# servos.net
KiCad netlist of a schematic drawn in Altium Designer
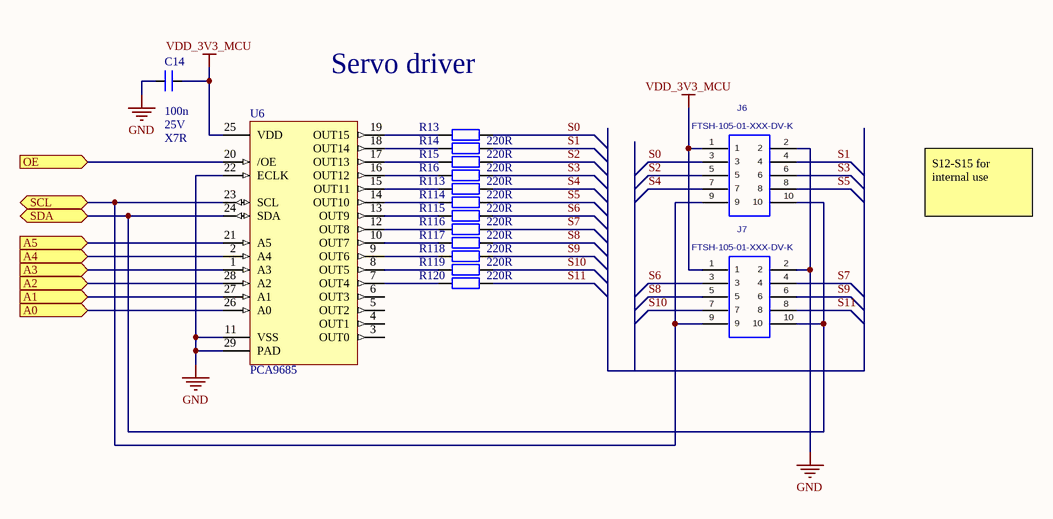
[diagram p0: servos.SchDoc]

(export (version "E")
  (design (tool "Eeschema 10.0.6"))
  (components
    (comp (ref "C14")
      (value "100n")
      (footprint "C1005[0402]")
      (description "Capacitor")
      (fields (field (name "VOLTAGE") "25V") (field (name "TYPE") "X7R") (field (name "Comment") "cap"))
      (libsource (lib "gpa_passives") (part "cap"))
    )
    (comp (ref "J6")
      (value "FTSH-105-01-XXX-DV-K")
      (footprint "FTSH-105-01-XXX-DV-K")
      (description "TERMINAL STRIP, .050\"(1.27mm) PITCH, 10 PINS, KEYED")
      (fields (field (name "MANUFACTURER") "SAMTEC") (field (name "CREATED") "November 30, 2016 - Wendy Xin"))
      (libsource (lib "FTSH-105-01-XXX-DV-K") (part "FTSH-105-01-XXX-DV-K"))
    )
    (comp (ref "J7")
      (value "FTSH-105-01-XXX-DV-K")
      (footprint "FTSH-105-01-XXX-DV-K")
      (description "TERMINAL STRIP, .050\"(1.27mm) PITCH, 10 PINS, KEYED")
      (fields (field (name "MANUFACTURER") "SAMTEC") (field (name "CREATED") "November 30, 2016 - Wendy Xin"))
      (libsource (lib "FTSH-105-01-XXX-DV-K") (part "FTSH-105-01-XXX-DV-K"))
    )
    (comp (ref "R13")
      (value "220R")
      (footprint "R1005[0402]")
      (description "Resistor")
      (fields (field (name "TOLERANCE") "5%") (field (name "Comment") "res"))
      (libsource (lib "gpa_passives") (part "res"))
    )
    (comp (ref "R14")
      (value "220R")
      (footprint "R1005[0402]")
      (description "Resistor")
      (fields (field (name "TOLERANCE") "5%") (field (name "Comment") "res"))
      (libsource (lib "gpa_passives") (part "res"))
    )
    (comp (ref "R15")
      (value "220R")
      (footprint "R1005[0402]")
      (description "Resistor")
      (fields (field (name "TOLERANCE") "5%") (field (name "Comment") "res"))
      (libsource (lib "gpa_passives") (part "res"))
    )
    (comp (ref "R16")
      (value "220R")
      (footprint "R1005[0402]")
      (description "Resistor")
      (fields (field (name "TOLERANCE") "5%") (field (name "Comment") "res"))
      (libsource (lib "gpa_passives") (part "res"))
    )
    (comp (ref "R113")
      (value "220R")
      (footprint "R1005[0402]")
      (description "Resistor")
      (fields (field (name "TOLERANCE") "5%") (field (name "Comment") "res"))
      (libsource (lib "gpa_passives") (part "res"))
    )
    (comp (ref "R114")
      (value "220R")
      (footprint "R1005[0402]")
      (description "Resistor")
      (fields (field (name "TOLERANCE") "5%") (field (name "Comment") "res"))
      (libsource (lib "gpa_passives") (part "res"))
    )
    (comp (ref "R115")
      (value "220R")
      (footprint "R1005[0402]")
      (description "Resistor")
      (fields (field (name "TOLERANCE") "5%") (field (name "Comment") "res"))
      (libsource (lib "gpa_passives") (part "res"))
    )
    (comp (ref "R116")
      (value "220R")
      (footprint "R1005[0402]")
      (description "Resistor")
      (fields (field (name "TOLERANCE") "5%") (field (name "Comment") "res"))
      (libsource (lib "gpa_passives") (part "res"))
    )
    (comp (ref "R117")
      (value "220R")
      (footprint "R1005[0402]")
      (description "Resistor")
      (fields (field (name "TOLERANCE") "5%") (field (name "Comment") "res"))
      (libsource (lib "gpa_passives") (part "res"))
    )
    (comp (ref "R118")
      (value "220R")
      (footprint "R1005[0402]")
      (description "Resistor")
      (fields (field (name "TOLERANCE") "5%") (field (name "Comment") "res"))
      (libsource (lib "gpa_passives") (part "res"))
    )
    (comp (ref "R119")
      (value "220R")
      (footprint "R1005[0402]")
      (description "Resistor")
      (fields (field (name "TOLERANCE") "5%") (field (name "Comment") "res"))
      (libsource (lib "gpa_passives") (part "res"))
    )
    (comp (ref "R120")
      (value "res")
      (footprint "R1005[0402]")
      (description "Resistor")
      (fields (field (name "TOLERANCE") "5%"))
      (libsource (lib "gpa_passives") (part "res"))
    )
    (comp (ref "U6")
      (value "PCA9685")
      (footprint "NXP_QFN65P600X600X100_HS-29M")
      (libsource (lib "gpa_nxp") (part "pca9685"))
    )
  )
  (nets
    (net (code "1") (name "/A0") (class "Default")
      (node (ref "U6") (pin "26") (pinfunction "A0_26") (pintype "input"))
    )
    (net (code "2") (name "/A1") (class "Default")
      (node (ref "U6") (pin "27") (pinfunction "A1_27") (pintype "input"))
    )
    (net (code "3") (name "/A2") (class "Default")
      (node (ref "U6") (pin "28") (pinfunction "A2_28") (pintype "input"))
    )
    (net (code "4") (name "/A3") (class "Default")
      (node (ref "U6") (pin "1") (pinfunction "A3_1") (pintype "input"))
    )
    (net (code "5") (name "/A4") (class "Default")
      (node (ref "U6") (pin "2") (pinfunction "A4_2") (pintype "input"))
    )
    (net (code "6") (name "/A5") (class "Default")
      (node (ref "U6") (pin "21") (pinfunction "A5_21") (pintype "input"))
    )
    (net (code "7") (name "/OE") (class "Default")
      (node (ref "U6") (pin "20") (pinfunction "/OE_20") (pintype "input"))
    )
    (net (code "8") (name "/S0") (class "Default")
      (node (ref "J6") (pin "3") (pinfunction "3_3") (pintype "passive"))
      (node (ref "R13") (pin "2") (pinfunction "2_2") (pintype "passive"))
    )
    (net (code "9") (name "/S1") (class "Default")
      (node (ref "J6") (pin "4") (pinfunction "4_4") (pintype "passive"))
      (node (ref "R14") (pin "2") (pinfunction "2_2") (pintype "passive"))
    )
    (net (code "10") (name "/S2") (class "Default")
      (node (ref "J6") (pin "5") (pinfunction "5_5") (pintype "passive"))
      (node (ref "R15") (pin "2") (pinfunction "2_2") (pintype "passive"))
    )
    (net (code "11") (name "/S3") (class "Default")
      (node (ref "J6") (pin "6") (pinfunction "6_6") (pintype "passive"))
      (node (ref "R16") (pin "2") (pinfunction "2_2") (pintype "passive"))
    )
    (net (code "12") (name "/S4") (class "Default")
      (node (ref "J6") (pin "7") (pinfunction "7_7") (pintype "passive"))
      (node (ref "R113") (pin "2") (pinfunction "2_2") (pintype "passive"))
    )
    (net (code "13") (name "/S5") (class "Default")
      (node (ref "J6") (pin "8") (pinfunction "8_8") (pintype "passive"))
      (node (ref "R114") (pin "2") (pinfunction "2_2") (pintype "passive"))
    )
    (net (code "14") (name "/S6") (class "Default")
      (node (ref "J7") (pin "3") (pinfunction "3_3") (pintype "passive"))
      (node (ref "R115") (pin "2") (pinfunction "2_2") (pintype "passive"))
    )
    (net (code "15") (name "/S7") (class "Default")
      (node (ref "J7") (pin "4") (pinfunction "4_4") (pintype "passive"))
      (node (ref "R116") (pin "2") (pinfunction "2_2") (pintype "passive"))
    )
    (net (code "16") (name "/S8") (class "Default")
      (node (ref "J7") (pin "5") (pinfunction "5_5") (pintype "passive"))
      (node (ref "R117") (pin "2") (pinfunction "2_2") (pintype "passive"))
    )
    (net (code "17") (name "/S9") (class "Default")
      (node (ref "J7") (pin "6") (pinfunction "6_6") (pintype "passive"))
      (node (ref "R118") (pin "2") (pinfunction "2_2") (pintype "passive"))
    )
    (net (code "18") (name "/S10") (class "Default")
      (node (ref "J7") (pin "7") (pinfunction "7_7") (pintype "passive"))
      (node (ref "R119") (pin "2") (pinfunction "2_2") (pintype "passive"))
    )
    (net (code "19") (name "/S11") (class "Default")
      (node (ref "J7") (pin "8") (pinfunction "8_8") (pintype "passive"))
      (node (ref "R120") (pin "2") (pinfunction "2_2") (pintype "passive"))
    )
    (net (code "20") (name "/SCL") (class "Default")
      (node (ref "J6") (pin "9") (pinfunction "9_9") (pintype "passive"))
      (node (ref "J7") (pin "9") (pinfunction "9_9") (pintype "passive"))
      (node (ref "U6") (pin "23") (pinfunction "SCL_23") (pintype "bidirectional"))
    )
    (net (code "21") (name "/SDA") (class "Default")
      (node (ref "J6") (pin "10") (pinfunction "10_10") (pintype "passive"))
      (node (ref "J7") (pin "10") (pinfunction "10_10") (pintype "passive"))
      (node (ref "U6") (pin "24") (pinfunction "SDA_24") (pintype "bidirectional"))
    )
    (net (code "22") (name "GND") (class "Default")
      (node (ref "C14") (pin "1") (pinfunction "1_1") (pintype "passive"))
      (node (ref "J6") (pin "2") (pinfunction "2_2") (pintype "passive"))
      (node (ref "J7") (pin "2") (pinfunction "2_2") (pintype "passive"))
      (node (ref "U6") (pin "11") (pinfunction "VSS_11") (pintype "power_in"))
      (node (ref "U6") (pin "22") (pinfunction "ECLK_22") (pintype "input"))
      (node (ref "U6") (pin "29") (pinfunction "PAD_29") (pintype "passive"))
    )
    (net (code "23") (name "Net-(U6-OUT4)") (class "Default")
      (node (ref "R120") (pin "1") (pinfunction "1_1") (pintype "passive"))
      (node (ref "U6") (pin "7") (pinfunction "OUT4_7") (pintype "output"))
    )
    (net (code "24") (name "Net-(U6-OUT5)") (class "Default")
      (node (ref "R119") (pin "1") (pinfunction "1_1") (pintype "passive"))
      (node (ref "U6") (pin "8") (pinfunction "OUT5_8") (pintype "output"))
    )
    (net (code "25") (name "Net-(U6-OUT6)") (class "Default")
      (node (ref "R118") (pin "1") (pinfunction "1_1") (pintype "passive"))
      (node (ref "U6") (pin "9") (pinfunction "OUT6_9") (pintype "output"))
    )
    (net (code "26") (name "Net-(U6-OUT7)") (class "Default")
      (node (ref "R117") (pin "1") (pinfunction "1_1") (pintype "passive"))
      (node (ref "U6") (pin "10") (pinfunction "OUT7_10") (pintype "output"))
    )
    (net (code "27") (name "Net-(U6-OUT8)") (class "Default")
      (node (ref "R116") (pin "1") (pinfunction "1_1") (pintype "passive"))
      (node (ref "U6") (pin "12") (pinfunction "OUT8_12") (pintype "output"))
    )
    (net (code "28") (name "Net-(U6-OUT9)") (class "Default")
      (node (ref "R115") (pin "1") (pinfunction "1_1") (pintype "passive"))
      (node (ref "U6") (pin "13") (pinfunction "OUT9_13") (pintype "output"))
    )
    (net (code "29") (name "Net-(U6-OUT10)") (class "Default")
      (node (ref "R114") (pin "1") (pinfunction "1_1") (pintype "passive"))
      (node (ref "U6") (pin "14") (pinfunction "OUT10_14") (pintype "output"))
    )
    (net (code "30") (name "Net-(U6-OUT11)") (class "Default")
      (node (ref "R113") (pin "1") (pinfunction "1_1") (pintype "passive"))
      (node (ref "U6") (pin "15") (pinfunction "OUT11_15") (pintype "output"))
    )
    (net (code "31") (name "Net-(U6-OUT12)") (class "Default")
      (node (ref "R16") (pin "1") (pinfunction "1_1") (pintype "passive"))
      (node (ref "U6") (pin "16") (pinfunction "OUT12_16") (pintype "output"))
    )
    (net (code "32") (name "Net-(U6-OUT13)") (class "Default")
      (node (ref "R15") (pin "1") (pinfunction "1_1") (pintype "passive"))
      (node (ref "U6") (pin "17") (pinfunction "OUT13_17") (pintype "output"))
    )
    (net (code "33") (name "Net-(U6-OUT14)") (class "Default")
      (node (ref "R14") (pin "1") (pinfunction "1_1") (pintype "passive"))
      (node (ref "U6") (pin "18") (pinfunction "OUT14_18") (pintype "output"))
    )
    (net (code "34") (name "Net-(U6-OUT15)") (class "Default")
      (node (ref "R13") (pin "1") (pinfunction "1_1") (pintype "passive"))
      (node (ref "U6") (pin "19") (pinfunction "OUT15_19") (pintype "output"))
    )
    (net (code "35") (name "VDD_3V3_MCU") (class "Default")
      (node (ref "C14") (pin "2") (pinfunction "2_2") (pintype "passive"))
      (node (ref "J6") (pin "1") (pinfunction "1_1") (pintype "passive"))
      (node (ref "J7") (pin "1") (pinfunction "1_1") (pintype "passive"))
      (node (ref "U6") (pin "25") (pinfunction "VDD_25") (pintype "power_in"))
    )
    (net (code "36") (name "unconnected-(U6-OUT0-Pad3)") (class "Default")
      (node (ref "U6") (pin "3") (pinfunction "OUT0_3") (pintype "output"))
    )
    (net (code "37") (name "unconnected-(U6-OUT1-Pad4)") (class "Default")
      (node (ref "U6") (pin "4") (pinfunction "OUT1_4") (pintype "output"))
    )
    (net (code "38") (name "unconnected-(U6-OUT2-Pad5)") (class "Default")
      (node (ref "U6") (pin "5") (pinfunction "OUT2_5") (pintype "output"))
    )
    (net (code "39") (name "unconnected-(U6-OUT3-Pad6)") (class "Default")
      (node (ref "U6") (pin "6") (pinfunction "OUT3_6") (pintype "output"))
    )
  )
)
